# 04-LcdTFT3_2inch.net
KiCad netlist of a schematic drawn in Altium Designer
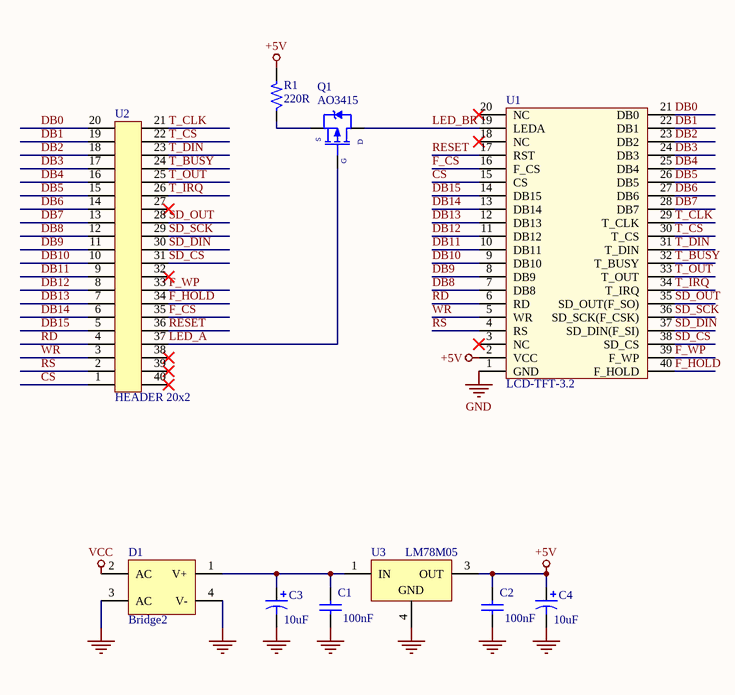
[diagram p0: 04-LcdTFT3.2inch.SchDoc]

(export (version "E")
  (design (tool "Eeschema 10.0.6"))
  (components
    (comp (ref "C1")
      (value "100nF")
      (footprint "RAD-0.3")
      (description "Capacitor")
      (fields (field (name "Comment") "104") (field (name "PUBLISHER") "Altium Limited"))
      (libsource (lib "Miscellaneous Devices") (part "Cap"))
    )
    (comp (ref "C2")
      (value "100nF")
      (footprint "RAD-0.3")
      (description "Capacitor")
      (fields (field (name "Comment") "104") (field (name "PUBLISHER") "Altium Limited"))
      (libsource (lib "Miscellaneous Devices") (part "Cap"))
    )
    (comp (ref "C3")
      (value "10uF")
      (footprint "RB7.6-15")
      (description "Polarized Capacitor (Radial)")
      (fields (field (name "Comment") "10uF/16V") (field (name "PUBLISHER") "Altium Limited"))
      (libsource (lib "Miscellaneous Devices") (part "Cap Pol1"))
    )
    (comp (ref "C4")
      (value "10uF")
      (footprint "RB7.6-15")
      (description "Polarized Capacitor (Radial)")
      (fields (field (name "Comment") "10uF/16V") (field (name "PUBLISHER") "Altium Limited"))
      (libsource (lib "Miscellaneous Devices") (part "Cap Pol1"))
    )
    (comp (ref "D1")
      (value "Bridge2")
      (footprint "D-46_6A")
      (description "Diode Bridge")
      (fields (field (name "PUBLISHER") "Altium Limited"))
      (libsource (lib "Miscellaneous Devices") (part "Bridge2"))
    )
    (comp (ref "Q1")
      (value "AO3415")
      (footprint "SOT-23-3")
      (description "HEXFET P-Channel Power MOSFET")
      (fields (field (name "PUBLISHER") "Altium Limited"))
      (libsource (lib "PART") (part "IRF9540"))
    )
    (comp (ref "R1")
      (value "220R")
      (footprint "R-0805")
      (description "Resistor 1/4W")
      (libsource (lib "syhaunguyen") (part "R"))
    )
    (comp (ref "U1")
      (value "LCD-TFT-3.2")
      (footprint "LCD-TFT-3.2'")
      (libsource (lib "doAnTotNghiep2017Lib") (part "LCD-TFT-3.2"))
    )
    (comp (ref "U2") (value "HEADER 20x2") (libsource (lib "doAnTotNghiep2017Lib") (part "JP20x2")))
    (comp (ref "U3")
      (value "LM78M05")
      (footprint "NDP0003B_M")
      (description "3-Terminal Positive Voltage Regulators, 3-pin TO-252")
      (fields (field (name "MANUFACTURER") "Texas Instruments") (field (name "Comment") "LM78M05CDTX"))
      (libsource (lib "Altium Content Vault") (part "CMP-0062-00204-3"))
    )
  )
  (nets
    (net (code "1") (name "+5V") (class "Default")
      (node (ref "C2") (pin "1") (pinfunction "1_1") (pintype "passive"))
      (node (ref "C4") (pin "1") (pinfunction "1_1") (pintype "passive"))
      (node (ref "R1") (pin "2") (pinfunction "2_2") (pintype "passive"))
      (node (ref "U1") (pin "2") (pinfunction "VCC_2") (pintype "passive"))
      (node (ref "U3") (pin "3") (pinfunction "OUT_3") (pintype "power_in"))
    )
    (net (code "2") (name "/CS") (class "Default")
      (node (ref "U1") (pin "15") (pinfunction "CS_15") (pintype "passive"))
      (node (ref "U2") (pin "1") (pintype "passive"))
    )
    (net (code "3") (name "/DB0") (class "Default")
      (node (ref "U1") (pin "21") (pinfunction "DB0_21") (pintype "passive"))
      (node (ref "U2") (pin "20") (pintype "passive"))
    )
    (net (code "4") (name "/DB1") (class "Default")
      (node (ref "U1") (pin "22") (pinfunction "DB1_22") (pintype "passive"))
      (node (ref "U2") (pin "19") (pintype "passive"))
    )
    (net (code "5") (name "/DB2") (class "Default")
      (node (ref "U1") (pin "23") (pinfunction "DB2_23") (pintype "passive"))
      (node (ref "U2") (pin "18") (pintype "passive"))
    )
    (net (code "6") (name "/DB3") (class "Default")
      (node (ref "U1") (pin "24") (pinfunction "DB3_24") (pintype "passive"))
      (node (ref "U2") (pin "17") (pintype "passive"))
    )
    (net (code "7") (name "/DB4") (class "Default")
      (node (ref "U1") (pin "25") (pinfunction "DB4_25") (pintype "passive"))
      (node (ref "U2") (pin "16") (pintype "passive"))
    )
    (net (code "8") (name "/DB5") (class "Default")
      (node (ref "U1") (pin "26") (pinfunction "DB5_26") (pintype "passive"))
      (node (ref "U2") (pin "15") (pintype "passive"))
    )
    (net (code "9") (name "/DB6") (class "Default")
      (node (ref "U1") (pin "27") (pinfunction "DB6_27") (pintype "passive"))
      (node (ref "U2") (pin "14") (pintype "passive"))
    )
    (net (code "10") (name "/DB7") (class "Default")
      (node (ref "U1") (pin "28") (pinfunction "DB7_28") (pintype "passive"))
      (node (ref "U2") (pin "13") (pintype "passive"))
    )
    (net (code "11") (name "/DB8") (class "Default")
      (node (ref "U1") (pin "7") (pinfunction "DB8_7") (pintype "passive"))
      (node (ref "U2") (pin "12") (pintype "passive"))
    )
    (net (code "12") (name "/DB9") (class "Default")
      (node (ref "U1") (pin "8") (pinfunction "DB9_8") (pintype "passive"))
      (node (ref "U2") (pin "11") (pintype "passive"))
    )
    (net (code "13") (name "/DB10") (class "Default")
      (node (ref "U1") (pin "9") (pinfunction "DB10_9") (pintype "passive"))
      (node (ref "U2") (pin "10") (pintype "passive"))
    )
    (net (code "14") (name "/DB11") (class "Default")
      (node (ref "U1") (pin "10") (pinfunction "DB11_10") (pintype "passive"))
      (node (ref "U2") (pin "9") (pintype "passive"))
    )
    (net (code "15") (name "/DB12") (class "Default")
      (node (ref "U1") (pin "11") (pinfunction "DB12_11") (pintype "passive"))
      (node (ref "U2") (pin "8") (pintype "passive"))
    )
    (net (code "16") (name "/DB13") (class "Default")
      (node (ref "U1") (pin "12") (pinfunction "DB13_12") (pintype "passive"))
      (node (ref "U2") (pin "7") (pintype "passive"))
    )
    (net (code "17") (name "/DB14") (class "Default")
      (node (ref "U1") (pin "13") (pinfunction "DB14_13") (pintype "passive"))
      (node (ref "U2") (pin "6") (pintype "passive"))
    )
    (net (code "18") (name "/DB15") (class "Default")
      (node (ref "U1") (pin "14") (pinfunction "DB15_14") (pintype "passive"))
      (node (ref "U2") (pin "5") (pintype "passive"))
    )
    (net (code "19") (name "/F_CS") (class "Default")
      (node (ref "U1") (pin "16") (pinfunction "F_CS_16") (pintype "passive"))
      (node (ref "U2") (pin "35") (pinfunction "35_35") (pintype "passive"))
    )
    (net (code "20") (name "/F_HOLD") (class "Default")
      (node (ref "U1") (pin "40") (pinfunction "F_HOLD_40") (pintype "passive"))
      (node (ref "U2") (pin "34") (pinfunction "34_34") (pintype "passive"))
    )
    (net (code "21") (name "/F_WP") (class "Default")
      (node (ref "U1") (pin "39") (pinfunction "F_WP_39") (pintype "passive"))
      (node (ref "U2") (pin "33") (pinfunction "33_33") (pintype "passive"))
    )
    (net (code "22") (name "/LED_A") (class "Default")
      (node (ref "Q1") (pin "1") (pinfunction "G_1") (pintype "passive"))
      (node (ref "U2") (pin "37") (pinfunction "37_37") (pintype "passive"))
    )
    (net (code "23") (name "/LED_BR") (class "Default")
      (node (ref "Q1") (pin "3") (pinfunction "D_3") (pintype "passive"))
      (node (ref "U1") (pin "19") (pinfunction "LEDA_19") (pintype "passive"))
    )
    (net (code "24") (name "/RD") (class "Default")
      (node (ref "U1") (pin "6") (pinfunction "RD_6") (pintype "passive"))
      (node (ref "U2") (pin "4") (pintype "passive"))
    )
    (net (code "25") (name "/RESET") (class "Default")
      (node (ref "U1") (pin "17") (pinfunction "RST_17") (pintype "passive"))
      (node (ref "U2") (pin "36") (pinfunction "36_36") (pintype "passive"))
    )
    (net (code "26") (name "/RS") (class "Default")
      (node (ref "U1") (pin "4") (pinfunction "RS_4") (pintype "passive"))
      (node (ref "U2") (pin "2") (pintype "passive"))
    )
    (net (code "27") (name "/SD_CS") (class "Default")
      (node (ref "U1") (pin "38") (pinfunction "SD_CS_38") (pintype "passive"))
      (node (ref "U2") (pin "31") (pinfunction "31_31") (pintype "passive"))
    )
    (net (code "28") (name "/SD_DIN") (class "Default")
      (node (ref "U1") (pin "37") (pinfunction "SD_DIN(F_SI)_37") (pintype "passive"))
      (node (ref "U2") (pin "30") (pinfunction "30_30") (pintype "passive"))
    )
    (net (code "29") (name "/SD_OUT") (class "Default")
      (node (ref "U1") (pin "35") (pinfunction "SD_OUT(F_SO)_35") (pintype "passive"))
      (node (ref "U2") (pin "28") (pinfunction "28_28") (pintype "passive"))
    )
    (net (code "30") (name "/SD_SCK") (class "Default")
      (node (ref "U1") (pin "36") (pinfunction "SD_SCK(F_CSK)_36") (pintype "passive"))
      (node (ref "U2") (pin "29") (pinfunction "29_29") (pintype "passive"))
    )
    (net (code "31") (name "/T_BUSY") (class "Default")
      (node (ref "U1") (pin "32") (pinfunction "T_BUSY_32") (pintype "passive"))
      (node (ref "U2") (pin "24") (pinfunction "24_24") (pintype "passive"))
    )
    (net (code "32") (name "/T_CLK") (class "Default")
      (node (ref "U1") (pin "29") (pinfunction "T_CLK_29") (pintype "passive"))
      (node (ref "U2") (pin "21") (pinfunction "21_21") (pintype "passive"))
    )
    (net (code "33") (name "/T_CS") (class "Default")
      (node (ref "U1") (pin "30") (pinfunction "T_CS_30") (pintype "passive"))
      (node (ref "U2") (pin "22") (pinfunction "22_22") (pintype "passive"))
    )
    (net (code "34") (name "/T_DIN") (class "Default")
      (node (ref "U1") (pin "31") (pinfunction "T_DIN_31") (pintype "passive"))
      (node (ref "U2") (pin "23") (pinfunction "23_23") (pintype "passive"))
    )
    (net (code "35") (name "/T_IRQ") (class "Default")
      (node (ref "U1") (pin "34") (pinfunction "T_IRQ_34") (pintype "passive"))
      (node (ref "U2") (pin "26") (pinfunction "26_26") (pintype "passive"))
    )
    (net (code "36") (name "/T_OUT") (class "Default")
      (node (ref "U1") (pin "33") (pinfunction "T_OUT_33") (pintype "passive"))
      (node (ref "U2") (pin "25") (pinfunction "25_25") (pintype "passive"))
    )
    (net (code "37") (name "/WR") (class "Default")
      (node (ref "U1") (pin "5") (pinfunction "WR_5") (pintype "passive"))
      (node (ref "U2") (pin "3") (pintype "passive"))
    )
    (net (code "38") (name "GND") (class "Default")
      (node (ref "C1") (pin "2") (pinfunction "2_2") (pintype "passive"))
      (node (ref "C2") (pin "2") (pinfunction "2_2") (pintype "passive"))
      (node (ref "C3") (pin "2") (pinfunction "2_2") (pintype "passive"))
      (node (ref "C4") (pin "2") (pinfunction "2_2") (pintype "passive"))
      (node (ref "D1") (pin "3") (pinfunction "AC_3") (pintype "passive"))
      (node (ref "D1") (pin "4") (pinfunction "V-_4") (pintype "passive"))
      (node (ref "U1") (pin "1") (pinfunction "GND_1") (pintype "passive"))
      (node (ref "U3") (pin "4") (pinfunction "GND_4") (pintype "power_in"))
    )
    (net (code "39") (name "Net-(D1-V+)") (class "Default")
      (node (ref "C1") (pin "1") (pinfunction "1_1") (pintype "passive"))
      (node (ref "C3") (pin "1") (pinfunction "1_1") (pintype "passive"))
      (node (ref "D1") (pin "1") (pinfunction "V+_1") (pintype "passive"))
      (node (ref "U3") (pin "1") (pinfunction "IN_1") (pintype "power_in"))
    )
    (net (code "40") (name "Net-(Q1-S)") (class "Default")
      (node (ref "Q1") (pin "2") (pinfunction "S_2") (pintype "passive"))
      (node (ref "R1") (pin "1") (pinfunction "1_1") (pintype "passive"))
    )
    (net (code "41") (name "VCC") (class "Default")
      (node (ref "D1") (pin "2") (pinfunction "AC_2") (pintype "passive"))
    )
    (net (code "42") (name "unconnected-(U1-NC-Pad3)") (class "Default")
      (node (ref "U1") (pin "3") (pinfunction "NC_3") (pintype "passive+no_connect"))
    )
    (net (code "43") (name "unconnected-(U1-NC-Pad18)") (class "Default")
      (node (ref "U1") (pin "18") (pinfunction "NC_18") (pintype "passive+no_connect"))
    )
    (net (code "44") (name "unconnected-(U1-NC-Pad20)") (class "Default")
      (node (ref "U1") (pin "20") (pinfunction "NC_20") (pintype "passive+no_connect"))
    )
    (net (code "45") (name "unconnected-(U2-Pad27)") (class "Default")
      (node (ref "U2") (pin "27") (pinfunction "27_27") (pintype "passive+no_connect"))
    )
    (net (code "46") (name "unconnected-(U2-Pad32)") (class "Default")
      (node (ref "U2") (pin "32") (pinfunction "32_32") (pintype "passive+no_connect"))
    )
    (net (code "47") (name "unconnected-(U2-Pad38)") (class "Default")
      (node (ref "U2") (pin "38") (pinfunction "38_38") (pintype "passive+no_connect"))
    )
    (net (code "48") (name "unconnected-(U2-Pad39)") (class "Default")
      (node (ref "U2") (pin "39") (pinfunction "39_39") (pintype "passive+no_connect"))
    )
    (net (code "49") (name "unconnected-(U2-Pad40)") (class "Default")
      (node (ref "U2") (pin "40") (pinfunction "40_40") (pintype "passive+no_connect"))
    )
  )
)
